# Sheet1.net
KiCad netlist of a schematic drawn in Altium Designer
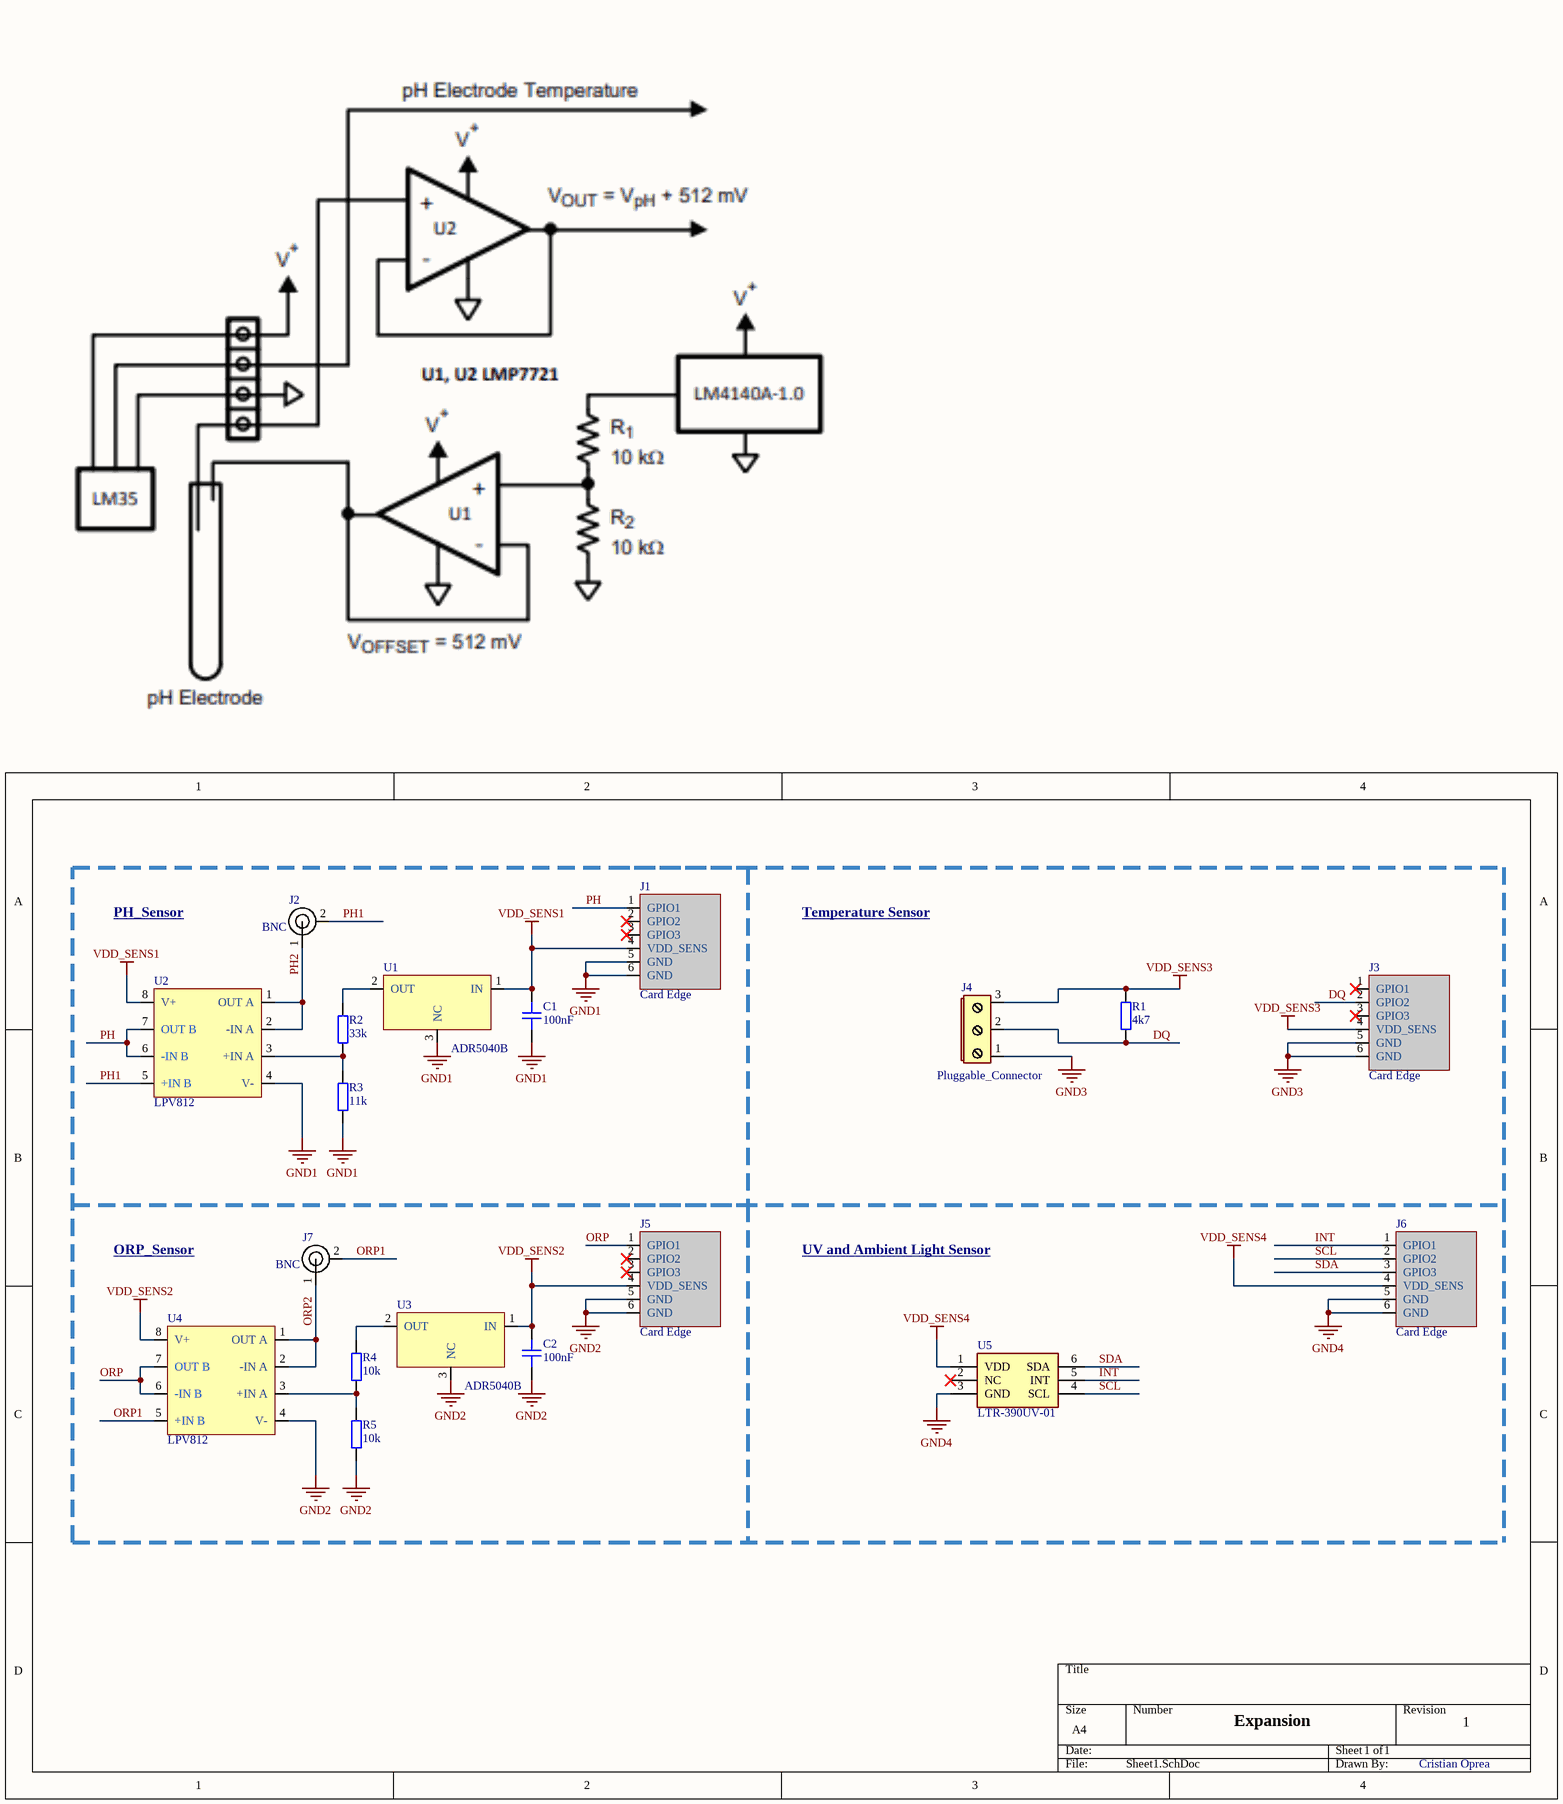
[diagram p0: Sheet1.SchDoc]

(export (version "E")
  (design (tool "Eeschema 10.0.6"))
  (components
    (comp (ref "C1")
      (value "100nF")
      (footprint "C0603")
      (description "Capacitor SMD 0603")
      (libsource (lib "Schlib1") (part "CAP_0603"))
    )
    (comp (ref "C2")
      (value "100nF")
      (footprint "C0603")
      (description "Capacitor SMD 0603")
      (libsource (lib "Schlib1") (part "CAP_0603"))
    )
    (comp (ref "J1")
      (value "Card Edge")
      (footprint "Card Edge")
      (description "Card Edge pads for 2.54 mm pitch edge connector")
      (libsource (lib "Schlib1") (part "Card Edge"))
    )
    (comp (ref "J2")
      (value "BNC")
      (footprint "CON_BNC_MOLEX_0731375003")
      (description "RF Connector BNC Female 50 Ohms PCB TH Mount")
      (fields
        (field (name "MANUFACTURER") "RF Solutions")
        (field (name "MANUFACTURER PART NUMBER") "CON-SMA-EDGE-S")
      )
      (libsource (lib "Schlib1") (part "CON-BNC"))
    )
    (comp (ref "J3")
      (value "Card Edge")
      (footprint "Card Edge")
      (description "Card Edge pads for 2.54 mm pitch edge connector")
      (libsource (lib "Schlib1") (part "Card Edge"))
    )
    (comp (ref "J4")
      (value "Pluggable_Connector")
      (description "Screw terminal or plug terminal")
      (libsource (lib "Schlib1") (part "Pluggable_Connector"))
    )
    (comp (ref "J5")
      (value "Card Edge")
      (footprint "Card Edge")
      (description "Card Edge pads for 2.54 mm pitch edge connector")
      (libsource (lib "Schlib1") (part "Card Edge"))
    )
    (comp (ref "J6")
      (value "Card Edge")
      (footprint "Card Edge")
      (description "Card Edge pads for 2.54 mm pitch edge connector")
      (libsource (lib "Schlib1") (part "Card Edge"))
    )
    (comp (ref "J7")
      (value "BNC")
      (footprint "CON_BNC_MOLEX_0731375003")
      (description "RF Connector BNC Female 50 Ohms PCB TH Mount")
      (fields
        (field (name "MANUFACTURER") "RF Solutions")
        (field (name "MANUFACTURER PART NUMBER") "CON-SMA-EDGE-S")
      )
      (libsource (lib "Schlib1") (part "CON-BNC"))
    )
    (comp (ref "R1")
      (value "4k7")
      (footprint "C0603")
      (description "Resistor SMD 0805")
      (libsource (lib "Schlib1") (part "RES_0805"))
    )
    (comp (ref "R2")
      (value "33k")
      (footprint "C0603")
      (description "Resistor SMD 0805")
      (libsource (lib "Schlib1") (part "RES_0805"))
    )
    (comp (ref "R3")
      (value "11k")
      (footprint "C0603")
      (description "Resistor SMD 0805")
      (libsource (lib "Schlib1") (part "RES_0805"))
    )
    (comp (ref "R4")
      (value "10k")
      (footprint "C0603")
      (description "Resistor SMD 0805")
      (libsource (lib "Schlib1") (part "RES_0805"))
    )
    (comp (ref "R5")
      (value "10k")
      (footprint "C0603")
      (description "Resistor SMD 0805")
      (libsource (lib "Schlib1") (part "RES_0805"))
    )
    (comp (ref "U1")
      (value "ADR5040B")
      (footprint "SOT23-3")
      (description "Voltage References 2.048 Low-Cost, Micropower, Low-Dropout, High-Output-Current, SOT23")
      (fields
        (field (name "MANUFACTURER") "Maxim Integrated")
        (field (name "MANUFACTURER PART NUMBER") "MAX6101EUR+T")
      )
      (libsource (lib "Schlib1") (part "VREF"))
    )
    (comp (ref "U2")
      (value "LPV812")
      (footprint "VSSOP 8")
      (description "Dual Channel 425nA Precision Nanopower Operational Amplifiers")
      (libsource (lib "Schlib1") (part "LPV812"))
    )
    (comp (ref "U3")
      (value "ADR5040B")
      (footprint "SOT23-3")
      (description "Voltage References 2.048 Low-Cost, Micropower, Low-Dropout, High-Output-Current, SOT23")
      (fields
        (field (name "MANUFACTURER") "Maxim Integrated")
        (field (name "MANUFACTURER PART NUMBER") "MAX6101EUR+T")
      )
      (libsource (lib "Schlib1") (part "VREF"))
    )
    (comp (ref "U4")
      (value "LPV812")
      (footprint "VSSOP 8")
      (description "Dual Channel 425nA Precision Nanopower Operational Amplifiers")
      (libsource (lib "Schlib1") (part "LPV812"))
    )
    (comp (ref "U5")
      (value "LTR-390UV-01")
      (footprint "LTR390UV01")
      (description "SENSOR OPT ULTRAVIOLET 6PINS")
      (fields (field (name "MOUSER PART NUMBER") "859-LTR390UV01"))
      (libsource (lib "Schlib1") (part "LTR-390UV-01"))
    )
  )
  (nets
    (net (code "1") (name "/DQ") (class "Default")
      (node (ref "J3") (pin "2") (pinfunction "GPIO2_2") (pintype "passive"))
      (node (ref "J4") (pin "2") (pinfunction "2_2") (pintype "passive"))
      (node (ref "R1") (pin "1") (pinfunction "1_1") (pintype "passive"))
    )
    (net (code "2") (name "/INT") (class "Default")
      (node (ref "J6") (pin "1") (pinfunction "GPIO1_1") (pintype "passive"))
      (node (ref "U5") (pin "5") (pinfunction "INT_5") (pintype "passive"))
    )
    (net (code "3") (name "/ORP") (class "Default")
      (node (ref "J5") (pin "1") (pinfunction "GPIO1_1") (pintype "passive"))
      (node (ref "U4") (pin "6") (pinfunction "-IN_B_6") (pintype "passive"))
      (node (ref "U4") (pin "7") (pinfunction "OUT_B_7") (pintype "passive"))
    )
    (net (code "4") (name "/ORP1") (class "Default")
      (node (ref "J7") (pin "2") (pinfunction "2_2") (pintype "passive"))
      (node (ref "U4") (pin "5") (pinfunction "+IN_B_5") (pintype "passive"))
    )
    (net (code "5") (name "/ORP2") (class "Default")
      (node (ref "J7") (pin "1") (pinfunction "1_1") (pintype "passive"))
      (node (ref "U4") (pin "1") (pinfunction "OUT_A_1") (pintype "passive"))
      (node (ref "U4") (pin "2") (pinfunction "-IN_A_2") (pintype "passive"))
    )
    (net (code "6") (name "/PH") (class "Default")
      (node (ref "J1") (pin "1") (pinfunction "GPIO1_1") (pintype "passive"))
      (node (ref "U2") (pin "6") (pinfunction "-IN_B_6") (pintype "passive"))
      (node (ref "U2") (pin "7") (pinfunction "OUT_B_7") (pintype "passive"))
    )
    (net (code "7") (name "/PH1") (class "Default")
      (node (ref "J2") (pin "2") (pinfunction "2_2") (pintype "passive"))
      (node (ref "U2") (pin "5") (pinfunction "+IN_B_5") (pintype "passive"))
    )
    (net (code "8") (name "/PH2") (class "Default")
      (node (ref "J2") (pin "1") (pinfunction "1_1") (pintype "passive"))
      (node (ref "U2") (pin "1") (pinfunction "OUT_A_1") (pintype "passive"))
      (node (ref "U2") (pin "2") (pinfunction "-IN_A_2") (pintype "passive"))
    )
    (net (code "9") (name "/SCL") (class "Default")
      (node (ref "J6") (pin "2") (pinfunction "GPIO2_2") (pintype "passive"))
      (node (ref "U5") (pin "4") (pinfunction "SCL_4") (pintype "passive"))
    )
    (net (code "10") (name "/SDA") (class "Default")
      (node (ref "J6") (pin "3") (pinfunction "GPIO3_3") (pintype "passive"))
      (node (ref "U5") (pin "6") (pinfunction "SDA_6") (pintype "passive"))
    )
    (net (code "11") (name "GND1") (class "Default")
      (node (ref "C1") (pin "1") (pinfunction "1_1") (pintype "passive"))
      (node (ref "J1") (pin "5") (pinfunction "GND_5") (pintype "passive"))
      (node (ref "J1") (pin "6") (pinfunction "GND_6") (pintype "passive"))
      (node (ref "R3") (pin "1") (pinfunction "1_1") (pintype "passive"))
      (node (ref "U1") (pin "3") (pinfunction "NC_3") (pintype "passive"))
      (node (ref "U2") (pin "4") (pinfunction "V-_4") (pintype "passive"))
    )
    (net (code "12") (name "GND2") (class "Default")
      (node (ref "C2") (pin "1") (pinfunction "1_1") (pintype "passive"))
      (node (ref "J5") (pin "5") (pinfunction "GND_5") (pintype "passive"))
      (node (ref "J5") (pin "6") (pinfunction "GND_6") (pintype "passive"))
      (node (ref "R5") (pin "1") (pinfunction "1_1") (pintype "passive"))
      (node (ref "U3") (pin "3") (pinfunction "NC_3") (pintype "passive"))
      (node (ref "U4") (pin "4") (pinfunction "V-_4") (pintype "passive"))
    )
    (net (code "13") (name "GND3") (class "Default")
      (node (ref "J3") (pin "5") (pinfunction "GND_5") (pintype "passive"))
      (node (ref "J3") (pin "6") (pinfunction "GND_6") (pintype "passive"))
      (node (ref "J4") (pin "1") (pinfunction "1_1") (pintype "passive"))
    )
    (net (code "14") (name "GND4") (class "Default")
      (node (ref "J6") (pin "5") (pinfunction "GND_5") (pintype "passive"))
      (node (ref "J6") (pin "6") (pinfunction "GND_6") (pintype "passive"))
      (node (ref "U5") (pin "3") (pinfunction "GND_3") (pintype "passive"))
    )
    (net (code "15") (name "Net-(U1-OUT)") (class "Default")
      (node (ref "R2") (pin "2") (pinfunction "2_2") (pintype "passive"))
      (node (ref "U1") (pin "2") (pinfunction "OUT_2") (pintype "passive"))
    )
    (net (code "16") (name "Net-(U2-+IN_A)") (class "Default")
      (node (ref "R2") (pin "1") (pinfunction "1_1") (pintype "passive"))
      (node (ref "R3") (pin "2") (pinfunction "2_2") (pintype "passive"))
      (node (ref "U2") (pin "3") (pinfunction "+IN_A_3") (pintype "passive"))
    )
    (net (code "17") (name "Net-(U3-OUT)") (class "Default")
      (node (ref "R4") (pin "2") (pinfunction "2_2") (pintype "passive"))
      (node (ref "U3") (pin "2") (pinfunction "OUT_2") (pintype "passive"))
    )
    (net (code "18") (name "Net-(U4-+IN_A)") (class "Default")
      (node (ref "R4") (pin "1") (pinfunction "1_1") (pintype "passive"))
      (node (ref "R5") (pin "2") (pinfunction "2_2") (pintype "passive"))
      (node (ref "U4") (pin "3") (pinfunction "+IN_A_3") (pintype "passive"))
    )
    (net (code "19") (name "VDD_SENS1") (class "Default")
      (node (ref "C1") (pin "2") (pinfunction "2_2") (pintype "passive"))
      (node (ref "J1") (pin "4") (pinfunction "VDD_SENS_4") (pintype "passive"))
      (node (ref "U1") (pin "1") (pinfunction "IN_1") (pintype "passive"))
      (node (ref "U2") (pin "8") (pinfunction "V+_8") (pintype "passive"))
    )
    (net (code "20") (name "VDD_SENS2") (class "Default")
      (node (ref "C2") (pin "2") (pinfunction "2_2") (pintype "passive"))
      (node (ref "J5") (pin "4") (pinfunction "VDD_SENS_4") (pintype "passive"))
      (node (ref "U3") (pin "1") (pinfunction "IN_1") (pintype "passive"))
      (node (ref "U4") (pin "8") (pinfunction "V+_8") (pintype "passive"))
    )
    (net (code "21") (name "VDD_SENS3") (class "Default")
      (node (ref "J3") (pin "4") (pinfunction "VDD_SENS_4") (pintype "passive"))
      (node (ref "J4") (pin "3") (pinfunction "3_3") (pintype "passive"))
      (node (ref "R1") (pin "2") (pinfunction "2_2") (pintype "passive"))
    )
    (net (code "22") (name "VDD_SENS4") (class "Default")
      (node (ref "J6") (pin "4") (pinfunction "VDD_SENS_4") (pintype "passive"))
      (node (ref "U5") (pin "1") (pinfunction "VDD_1") (pintype "passive"))
    )
    (net (code "23") (name "unconnected-(J1-GPIO2-Pad2)") (class "Default")
      (node (ref "J1") (pin "2") (pinfunction "GPIO2_2") (pintype "passive+no_connect"))
    )
    (net (code "24") (name "unconnected-(J1-GPIO3-Pad3)") (class "Default")
      (node (ref "J1") (pin "3") (pinfunction "GPIO3_3") (pintype "passive+no_connect"))
    )
    (net (code "25") (name "unconnected-(J3-GPIO1-Pad1)") (class "Default")
      (node (ref "J3") (pin "1") (pinfunction "GPIO1_1") (pintype "passive+no_connect"))
    )
    (net (code "26") (name "unconnected-(J3-GPIO3-Pad3)") (class "Default")
      (node (ref "J3") (pin "3") (pinfunction "GPIO3_3") (pintype "passive+no_connect"))
    )
    (net (code "27") (name "unconnected-(J5-GPIO2-Pad2)") (class "Default")
      (node (ref "J5") (pin "2") (pinfunction "GPIO2_2") (pintype "passive+no_connect"))
    )
    (net (code "28") (name "unconnected-(J5-GPIO3-Pad3)") (class "Default")
      (node (ref "J5") (pin "3") (pinfunction "GPIO3_3") (pintype "passive+no_connect"))
    )
    (net (code "29") (name "unconnected-(U5-NC-Pad2)") (class "Default")
      (node (ref "U5") (pin "2") (pinfunction "NC_2") (pintype "passive+no_connect"))
    )
  )
)
